# ePaperShoe.net
KiCad netlist of a schematic drawn in EAGLE
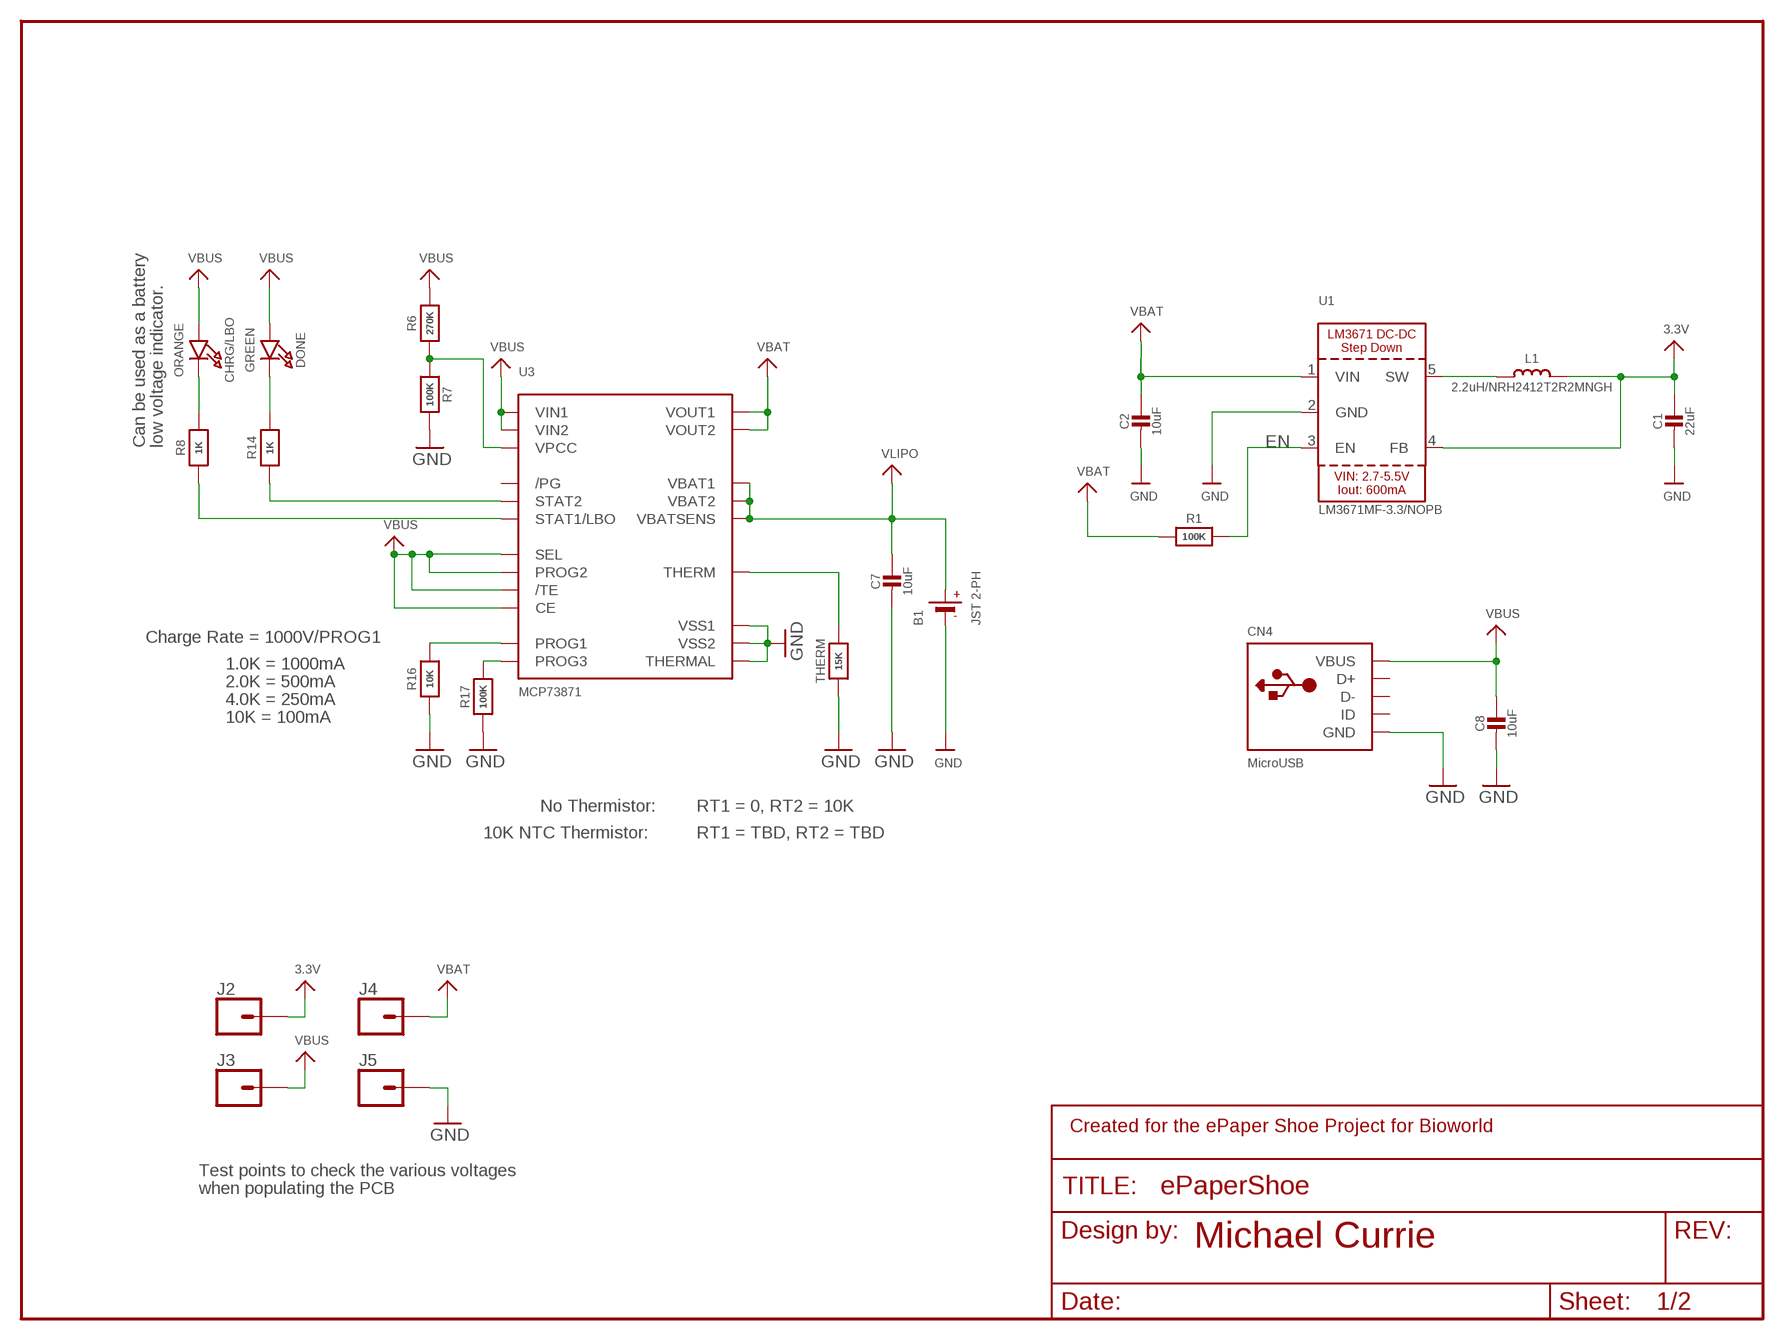
[diagram p0: schematic, sheet 1]
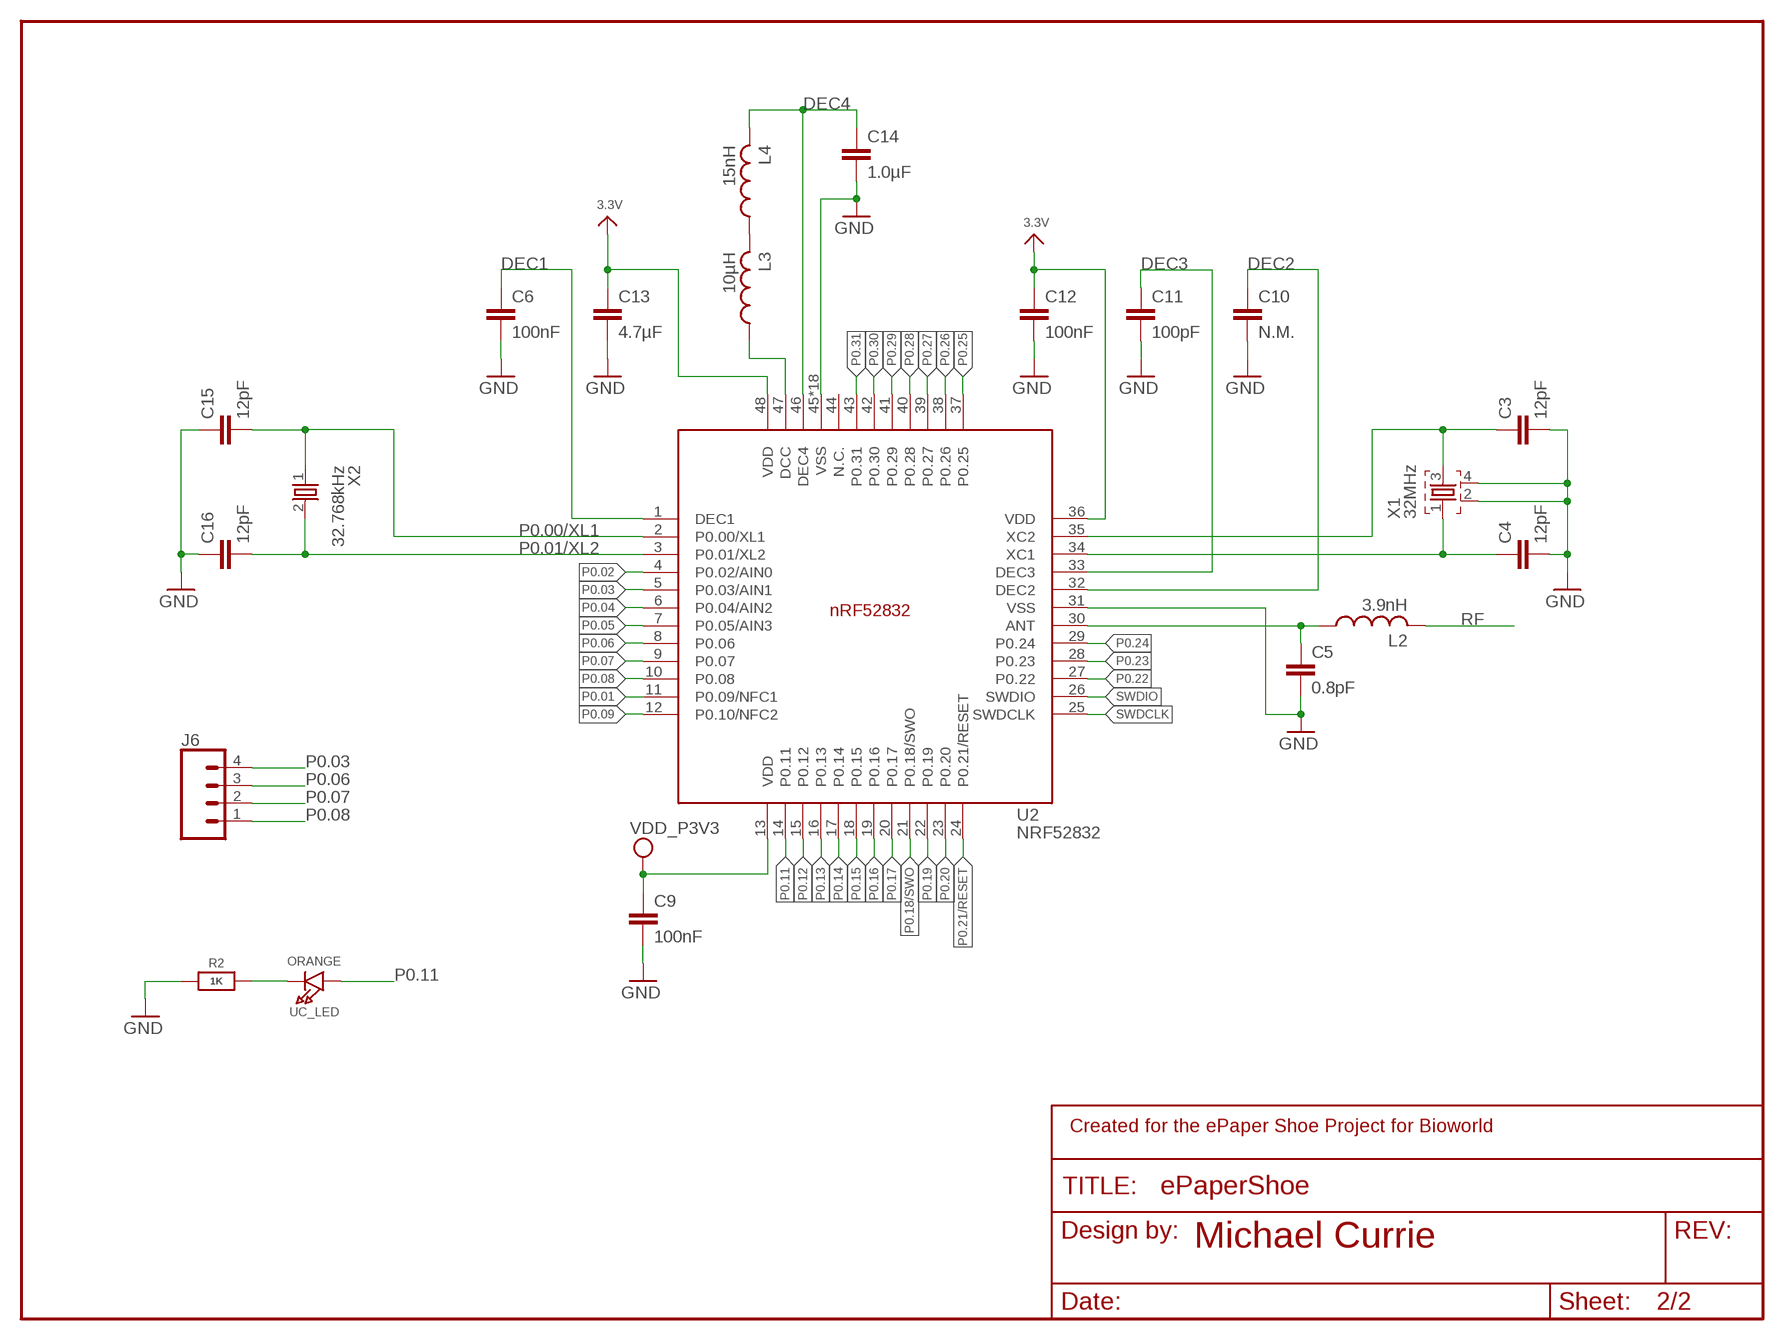
[diagram p1: schematic, sheet 2]

(export (version "E")
  (design (tool "Eeschema 10.0.6"))
  (components
    (comp (ref "B1")
      (value "JST 2-PH")
      (footprint "eagle-import:JSTPH2")
      (libsource (lib "eagle-import") (part "BATTERY"))
    )
    (comp (ref "C1")
      (value "22uF")
      (footprint "eagle-import:0805-NO")
      (libsource (lib "eagle-import") (part "CAP_CERAMIC0805-NOOUTLINE"))
    )
    (comp (ref "C2")
      (value "10uF")
      (footprint "eagle-import:0805-NO")
      (libsource (lib "eagle-import") (part "CAP_CERAMIC0805-NOOUTLINE"))
    )
    (comp (ref "C7")
      (value "10uF")
      (footprint "eagle-import:0805-NO")
      (libsource (lib "eagle-import") (part "CAP_CERAMIC0805-NOOUTLINE"))
    )
    (comp (ref "C8")
      (value "10uF")
      (footprint "eagle-import:0805-NO")
      (libsource (lib "eagle-import") (part "CAP_CERAMIC0805-NOOUTLINE"))
    )
    (comp (ref "CHRG/LBO")
      (value "ORANGE")
      (footprint "eagle-import:CHIPLED_0805_NOOUTLINE")
      (libsource (lib "eagle-import") (part "LED0805_NOOUTLINE"))
    )
    (comp (ref "CN4")
      (value "MicroUSB")
      (footprint "eagle-import:4UCONN_20329")
      (libsource (lib "eagle-import") (part "USBMICRO_20329"))
    )
    (comp (ref "DONE")
      (value "GREEN")
      (footprint "eagle-import:CHIPLED_0805_NOOUTLINE")
      (libsource (lib "eagle-import") (part "LED0805_NOOUTLINE"))
    )
    (comp (ref "FRAME1")
      (value "FRAME-LETTER-MICHAELNO_PACKAGE")
      (footprint "eagle-import:DUMMY")
      (fields (field (name "DESIGNER") "Nobody"))
      (libsource (lib "eagle-import") (part "FRAME-LETTER-MICHAELNO_PACKAGE"))
    )
    (comp (ref "J2")
      (value "CONN_01")
      (footprint "eagle-import:1X01")
      (libsource (lib "eagle-import") (part "CONN_01"))
    )
    (comp (ref "J3")
      (value "CONN_01")
      (footprint "eagle-import:1X01")
      (libsource (lib "eagle-import") (part "CONN_01"))
    )
    (comp (ref "J4")
      (value "CONN_01")
      (footprint "eagle-import:1X01")
      (libsource (lib "eagle-import") (part "CONN_01"))
    )
    (comp (ref "J5")
      (value "CONN_01")
      (footprint "eagle-import:1X01")
      (libsource (lib "eagle-import") (part "CONN_01"))
    )
    (comp (ref "L1")
      (value "2.2uH/NRH2412T2R2MNGH")
      (footprint "eagle-import:INDUCTOR_TAIYOYUDEN_NRH2412T")
      (libsource (lib "eagle-import") (part "INDUCTORNRH2412T"))
    )
    (comp (ref "R1")
      (value "100K")
      (footprint "eagle-import:0805-NO")
      (libsource (lib "eagle-import") (part "RESISTOR0805_NOOUTLINE"))
    )
    (comp (ref "R6")
      (value "270K")
      (footprint "eagle-import:0805-NO")
      (libsource (lib "eagle-import") (part "RESISTOR0805_NOOUTLINE"))
    )
    (comp (ref "R7")
      (value "100K")
      (footprint "eagle-import:0805-NO")
      (libsource (lib "eagle-import") (part "RESISTOR0805_NOOUTLINE"))
    )
    (comp (ref "R8")
      (value "1K")
      (footprint "eagle-import:0805-NO")
      (libsource (lib "eagle-import") (part "RESISTOR0805_NOOUTLINE"))
    )
    (comp (ref "R14")
      (value "1K")
      (footprint "eagle-import:0805-NO")
      (libsource (lib "eagle-import") (part "RESISTOR0805_NOOUTLINE"))
    )
    (comp (ref "R16")
      (value "10K")
      (footprint "eagle-import:0805-NO")
      (libsource (lib "eagle-import") (part "RESISTOR0805_NOOUTLINE"))
    )
    (comp (ref "R17")
      (value "100K")
      (footprint "eagle-import:0805-NO")
      (libsource (lib "eagle-import") (part "RESISTOR0805_NOOUTLINE"))
    )
    (comp (ref "THERM")
      (value "15K")
      (footprint "eagle-import:0805-NO")
      (libsource (lib "eagle-import") (part "RESISTOR0805_NOOUTLINE"))
    )
    (comp (ref "U1")
      (value "LM3671MF-3.3/NOPB")
      (footprint "eagle-import:SOT23-5")
      (libsource (lib "eagle-import") (part "VREG_LM3671"))
    )
    (comp (ref "U3")
      (value "MCP73871")
      (footprint "eagle-import:QFN20_4MM")
      (libsource (lib "eagle-import") (part "MCP73871"))
    )
    (comp (ref "C3")
      (value "12pF")
      (footprint "eagle-import:RESC0402_N")
      (libsource (lib "eagle-import") (part "CAPACITOR_0402_N"))
    )
    (comp (ref "C4")
      (value "12pF")
      (footprint "eagle-import:RESC0402_N")
      (libsource (lib "eagle-import") (part "CAPACITOR_0402_N"))
    )
    (comp (ref "C5")
      (value "0.8pF")
      (footprint "eagle-import:RESC0402_N")
      (libsource (lib "eagle-import") (part "CAPACITOR_0402_N"))
    )
    (comp (ref "C6")
      (value "100nF")
      (footprint "eagle-import:RESC0402_N")
      (libsource (lib "eagle-import") (part "CAPACITOR_0402_N"))
    )
    (comp (ref "C9")
      (value "100nF")
      (footprint "eagle-import:RESC0402_N")
      (libsource (lib "eagle-import") (part "CAPACITOR_0402_N"))
    )
    (comp (ref "C10")
      (value "N.M.")
      (footprint "eagle-import:RESC0402_N")
      (libsource (lib "eagle-import") (part "CAPACITOR_0402_N"))
    )
    (comp (ref "C11")
      (value "100pF")
      (footprint "eagle-import:RESC0402_N")
      (libsource (lib "eagle-import") (part "CAPACITOR_0402_N"))
    )
    (comp (ref "C12")
      (value "100nF")
      (footprint "eagle-import:RESC0402_N")
      (libsource (lib "eagle-import") (part "CAPACITOR_0402_N"))
    )
    (comp (ref "C13")
      (value "4.7µF")
      (footprint "eagle-import:RESC0603_N")
      (libsource (lib "eagle-import") (part "CAPACITOR_0603_N"))
    )
    (comp (ref "C14")
      (value "1.0µF")
      (footprint "eagle-import:RESC0603_N")
      (libsource (lib "eagle-import") (part "CAPACITOR_0603_N"))
    )
    (comp (ref "C15")
      (value "12pF")
      (footprint "eagle-import:RESC0402_N")
      (libsource (lib "eagle-import") (part "CAPACITOR_0402_N"))
    )
    (comp (ref "C16")
      (value "12pF")
      (footprint "eagle-import:RESC0402_N")
      (libsource (lib "eagle-import") (part "CAPACITOR_0402_N"))
    )
    (comp (ref "FRAME2")
      (value "FRAME-LETTER-MICHAELNO_PACKAGE")
      (footprint "eagle-import:DUMMY")
      (fields (field (name "DESIGNER") "Nobody"))
      (libsource (lib "eagle-import") (part "FRAME-LETTER-MICHAELNO_PACKAGE"))
    )
    (comp (ref "J6")
      (value "CONN_04")
      (footprint "eagle-import:1X04")
      (libsource (lib "eagle-import") (part "CONN_04"))
    )
    (comp (ref "L2")
      (value "3.9nH")
      (footprint "eagle-import:RESC0402_N")
      (libsource (lib "eagle-import") (part "INDUCTOR_0402_N"))
    )
    (comp (ref "L3")
      (value "10µH")
      (footprint "eagle-import:RESC0603_N")
      (libsource (lib "eagle-import") (part "INDUCTOR_0603_N"))
    )
    (comp (ref "L4")
      (value "15nH")
      (footprint "eagle-import:RESC0402_N")
      (libsource (lib "eagle-import") (part "INDUCTOR_0402_N"))
    )
    (comp (ref "R2")
      (value "1K")
      (footprint "eagle-import:0805-NO")
      (libsource (lib "eagle-import") (part "RESISTOR0805_NOOUTLINE"))
    )
    (comp (ref "U2")
      (value "NRF52832")
      (footprint "eagle-import:QFN40P600X600X90-48_N")
      (libsource (lib "eagle-import") (part "NRF52832"))
    )
    (comp (ref "UC_LED")
      (value "ORANGE")
      (footprint "eagle-import:CHIPLED_0805_NOOUTLINE")
      (libsource (lib "eagle-import") (part "LED0805_NOOUTLINE"))
    )
    (comp (ref "X1")
      (value "32MHz")
      (footprint "eagle-import:BT-XTAL_2016_N")
      (libsource (lib "eagle-import") (part "XTAL_32MHZ"))
    )
    (comp (ref "X2")
      (value "32.768kHz")
      (footprint "eagle-import:XTAL_3215_N")
      (libsource (lib "eagle-import") (part "XTAL_32KHZ"))
    )
  )
  (nets
    (net (code "1") (name "3.3V") (class "Default")
      (node (ref "C1") (pin "1") (pinfunction "1_1") (pintype "passive"))
      (node (ref "C12") (pin "1") (pinfunction "1_1") (pintype "passive"))
      (node (ref "C13") (pin "1") (pinfunction "1_1") (pintype "passive"))
      (node (ref "J2") (pin "1") (pinfunction "1_1") (pintype "passive"))
      (node (ref "L1") (pin "2") (pinfunction "2_2") (pintype "passive"))
      (node (ref "U1") (pin "4") (pinfunction "FB_4") (pintype "power_in"))
      (node (ref "U2") (pin "36") (pinfunction "VDD_36") (pintype "power_in"))
      (node (ref "U2") (pin "48") (pinfunction "VDD_48") (pintype "power_in"))
    )
    (net (code "2") (name "DEC1") (class "Default")
      (node (ref "C6") (pin "1") (pinfunction "1_1") (pintype "passive"))
      (node (ref "U2") (pin "1") (pinfunction "DEC1_1") (pintype "power_in"))
    )
    (net (code "3") (name "DEC2") (class "Default")
      (node (ref "C10") (pin "1") (pinfunction "1_1") (pintype "passive"))
      (node (ref "U2") (pin "32") (pinfunction "DEC2_32") (pintype "bidirectional"))
    )
    (net (code "4") (name "DEC3") (class "Default")
      (node (ref "C11") (pin "1") (pinfunction "1_1") (pintype "passive"))
      (node (ref "U2") (pin "33") (pinfunction "DEC3_33") (pintype "bidirectional"))
    )
    (net (code "5") (name "DEC4") (class "Default")
      (node (ref "C14") (pin "1") (pinfunction "1_1") (pintype "passive"))
      (node (ref "L4") (pin "2") (pinfunction "2_2") (pintype "passive"))
      (node (ref "U2") (pin "46") (pinfunction "DEC4_46") (pintype "power_in"))
    )
    (net (code "6") (name "EN") (class "Default")
      (node (ref "R1") (pin "2") (pinfunction "2_2") (pintype "passive"))
      (node (ref "U1") (pin "3") (pinfunction "EN_3") (pintype "input"))
    )
    (net (code "7") (name "GND") (class "Default")
      (node (ref "B1") (pin "1") (pinfunction "-_1") (pintype "passive"))
      (node (ref "C1") (pin "2") (pinfunction "2_2") (pintype "passive"))
      (node (ref "C10") (pin "2") (pinfunction "2_2") (pintype "passive"))
      (node (ref "C11") (pin "2") (pinfunction "2_2") (pintype "passive"))
      (node (ref "C12") (pin "2") (pinfunction "2_2") (pintype "passive"))
      (node (ref "C13") (pin "2") (pinfunction "2_2") (pintype "passive"))
      (node (ref "C14") (pin "2") (pinfunction "2_2") (pintype "passive"))
      (node (ref "C15") (pin "1") (pinfunction "1_1") (pintype "passive"))
      (node (ref "C16") (pin "1") (pinfunction "1_1") (pintype "passive"))
      (node (ref "C2") (pin "2") (pinfunction "2_2") (pintype "passive"))
      (node (ref "C3") (pin "2") (pinfunction "2_2") (pintype "passive"))
      (node (ref "C4") (pin "2") (pinfunction "2_2") (pintype "passive"))
      (node (ref "C5") (pin "2") (pinfunction "2_2") (pintype "passive"))
      (node (ref "C6") (pin "2") (pinfunction "2_2") (pintype "passive"))
      (node (ref "C7") (pin "2") (pinfunction "2_2") (pintype "passive"))
      (node (ref "C8") (pin "2") (pinfunction "2_2") (pintype "passive"))
      (node (ref "C9") (pin "2") (pinfunction "2_2") (pintype "passive"))
      (node (ref "CN4") (pin "BASE@1") (pinfunction "GND_BASE@1") (pintype "power_in"))
      (node (ref "CN4") (pin "BASE@2") (pinfunction "GND_BASE@2") (pintype "power_in"))
      (node (ref "CN4") (pin "GND") (pinfunction "GND_GND") (pintype "power_in"))
      (node (ref "CN4") (pin "SPRT@1") (pinfunction "GND_SPRT@1") (pintype "power_in"))
      (node (ref "CN4") (pin "SPRT@2") (pinfunction "GND_SPRT@2") (pintype "power_in"))
      (node (ref "CN4") (pin "SPRT@3") (pinfunction "GND_SPRT@3") (pintype "power_in"))
      (node (ref "CN4") (pin "SPRT@4") (pinfunction "GND_SPRT@4") (pintype "power_in"))
      (node (ref "J5") (pin "1") (pinfunction "1_1") (pintype "passive"))
      (node (ref "R16") (pin "1") (pinfunction "1_1") (pintype "passive"))
      (node (ref "R17") (pin "1") (pinfunction "1_1") (pintype "passive"))
      (node (ref "R2") (pin "1") (pinfunction "1_1") (pintype "passive"))
      (node (ref "R7") (pin "2") (pinfunction "2_2") (pintype "passive"))
      (node (ref "THERM") (pin "1") (pinfunction "1_1") (pintype "passive"))
      (node (ref "U1") (pin "2") (pinfunction "GND_2") (pintype "power_in"))
      (node (ref "U2") (pin "31") (pinfunction "VSS_31") (pintype "bidirectional"))
      (node (ref "U2") (pin "45") (pinfunction "VSS_45") (pintype "power_in"))
      (node (ref "U2") (pin "PAD") (pinfunction "VSS_PAD") (pintype "power_in"))
      (node (ref "U2") (pin "PAD@VIA01") (pinfunction "VSS_PAD@VIA01") (pintype "power_in"))
      (node (ref "U2") (pin "PAD@VIA02") (pinfunction "VSS_PAD@VIA02") (pintype "power_in"))
      (node (ref "U2") (pin "PAD@VIA03") (pinfunction "VSS_PAD@VIA03") (pintype "power_in"))
      (node (ref "U2") (pin "PAD@VIA04") (pinfunction "VSS_PAD@VIA04") (pintype "power_in"))
      (node (ref "U2") (pin "PAD@VIA05") (pinfunction "VSS_PAD@VIA05") (pintype "power_in"))
      (node (ref "U2") (pin "PAD@VIA06") (pinfunction "VSS_PAD@VIA06") (pintype "power_in"))
      (node (ref "U2") (pin "PAD@VIA07") (pinfunction "VSS_PAD@VIA07") (pintype "power_in"))
      (node (ref "U2") (pin "PAD@VIA08") (pinfunction "VSS_PAD@VIA08") (pintype "power_in"))
      (node (ref "U2") (pin "PAD@VIA09") (pinfunction "VSS_PAD@VIA09") (pintype "power_in"))
      (node (ref "U2") (pin "PAD@VIA10") (pinfunction "VSS_PAD@VIA10") (pintype "power_in"))
      (node (ref "U2") (pin "PAD@VIA11") (pinfunction "VSS_PAD@VIA11") (pintype "power_in"))
      (node (ref "U2") (pin "PAD@VIA12") (pinfunction "VSS_PAD@VIA12") (pintype "power_in"))
      (node (ref "U2") (pin "PAD@VIA13") (pinfunction "VSS_PAD@VIA13") (pintype "power_in"))
      (node (ref "U2") (pin "PAD@VIA14") (pinfunction "VSS_PAD@VIA14") (pintype "power_in"))
      (node (ref "U2") (pin "PAD@VIA15") (pinfunction "VSS_PAD@VIA15") (pintype "power_in"))
      (node (ref "U2") (pin "PAD@VIA16") (pinfunction "VSS_PAD@VIA16") (pintype "power_in"))
      (node (ref "U3") (pin "P$10") (pinfunction "VSS1_P$10") (pintype "bidirectional"))
      (node (ref "U3") (pin "P$11") (pinfunction "VSS2_P$11") (pintype "bidirectional"))
      (node (ref "U3") (pin "P$21") (pinfunction "THERMAL_P$21") (pintype "bidirectional"))
      (node (ref "X1") (pin "2") (pinfunction "2_2") (pintype "passive"))
      (node (ref "X1") (pin "4") (pinfunction "4_4") (pintype "passive"))
    )
    (net (code "8") (name "Net-(CHRG/LBO-PadC)") (class "Default")
      (node (ref "CHRG/LBO") (pin "C") (pinfunction "C_C") (pintype "passive"))
      (node (ref "R8") (pin "2") (pinfunction "2_2") (pintype "passive"))
    )
    (net (code "9") (name "Net-(DONE-PadC)") (class "Default")
      (node (ref "DONE") (pin "C") (pinfunction "C_C") (pintype "passive"))
      (node (ref "R14") (pin "2") (pinfunction "2_2") (pintype "passive"))
    )
    (net (code "10") (name "Net-(L3-Pad2)") (class "Default")
      (node (ref "L3") (pin "2") (pinfunction "2_2") (pintype "passive"))
      (node (ref "L4") (pin "1") (pinfunction "1_1") (pintype "passive"))
    )
    (net (code "11") (name "Net-(R2-Pad2)") (class "Default")
      (node (ref "R2") (pin "2") (pinfunction "2_2") (pintype "passive"))
      (node (ref "UC_LED") (pin "C") (pinfunction "C_C") (pintype "passive"))
    )
    (net (code "12") (name "Net-(U1-SW)") (class "Default")
      (node (ref "L1") (pin "1") (pinfunction "1_1") (pintype "passive"))
      (node (ref "U1") (pin "5") (pinfunction "SW_5") (pintype "output"))
    )
    (net (code "13") (name "Net-(U2-ANT)") (class "Default")
      (node (ref "C5") (pin "1") (pinfunction "1_1") (pintype "passive"))
      (node (ref "L2") (pin "1") (pinfunction "1_1") (pintype "passive"))
      (node (ref "U2") (pin "30") (pinfunction "ANT_30") (pintype "bidirectional"))
    )
    (net (code "14") (name "Net-(U2-DCC)") (class "Default")
      (node (ref "L3") (pin "1") (pinfunction "1_1") (pintype "passive"))
      (node (ref "U2") (pin "47") (pinfunction "DCC_47") (pintype "output"))
    )
    (net (code "15") (name "Net-(U2-XC1)") (class "Default")
      (node (ref "C4") (pin "1") (pinfunction "1_1") (pintype "passive"))
      (node (ref "U2") (pin "34") (pinfunction "XC1_34") (pintype "input"))
      (node (ref "X1") (pin "1") (pinfunction "1_1") (pintype "passive"))
    )
    (net (code "16") (name "Net-(U2-XC2)") (class "Default")
      (node (ref "C3") (pin "1") (pinfunction "1_1") (pintype "passive"))
      (node (ref "U2") (pin "35") (pinfunction "XC2_35") (pintype "output"))
      (node (ref "X1") (pin "3") (pinfunction "3_3") (pintype "passive"))
    )
    (net (code "17") (name "Net-(U3-PROG1)") (class "Default")
      (node (ref "R16") (pin "2") (pinfunction "2_2") (pintype "passive"))
      (node (ref "U3") (pin "P$13") (pinfunction "PROG1_P$13") (pintype "bidirectional"))
    )
    (net (code "18") (name "Net-(U3-PROG3)") (class "Default")
      (node (ref "R17") (pin "2") (pinfunction "2_2") (pintype "passive"))
      (node (ref "U3") (pin "P$12") (pinfunction "PROG3_P$12") (pintype "bidirectional"))
    )
    (net (code "19") (name "Net-(U3-STAT1{slash}LBO)") (class "Default")
      (node (ref "R8") (pin "1") (pinfunction "1_1") (pintype "passive"))
      (node (ref "U3") (pin "P$8") (pinfunction "STAT1/LBO_P$8") (pintype "bidirectional"))
    )
    (net (code "20") (name "Net-(U3-STAT2)") (class "Default")
      (node (ref "R14") (pin "1") (pinfunction "1_1") (pintype "passive"))
      (node (ref "U3") (pin "P$7") (pinfunction "STAT2_P$7") (pintype "bidirectional"))
    )
    (net (code "21") (name "Net-(U3-THERM)") (class "Default")
      (node (ref "THERM") (pin "2") (pinfunction "2_2") (pintype "passive"))
      (node (ref "U3") (pin "P$5") (pinfunction "THERM_P$5") (pintype "bidirectional"))
    )
    (net (code "22") (name "Net-(U3-VPCC)") (class "Default")
      (node (ref "R6") (pin "1") (pinfunction "1_1") (pintype "passive"))
      (node (ref "R7") (pin "1") (pinfunction "1_1") (pintype "passive"))
      (node (ref "U3") (pin "P$2") (pinfunction "VPCC_P$2") (pintype "bidirectional"))
    )
    (net (code "23") (name "P0.00{slash}XL1") (class "Default")
      (node (ref "C15") (pin "2") (pinfunction "2_2") (pintype "passive"))
      (node (ref "U2") (pin "2") (pinfunction "P0.00/XL1_2") (pintype "bidirectional"))
      (node (ref "X2") (pin "1") (pinfunction "1_1") (pintype "passive"))
    )
    (net (code "24") (name "P0.01") (class "Default")
      (node (ref "U2") (pin "11") (pinfunction "P0.09/NFC1_11") (pintype "bidirectional"))
    )
    (net (code "25") (name "P0.01{slash}XL2") (class "Default")
      (node (ref "C16") (pin "2") (pinfunction "2_2") (pintype "passive"))
      (node (ref "U2") (pin "3") (pinfunction "P0.01/XL2_3") (pintype "bidirectional"))
      (node (ref "X2") (pin "2") (pinfunction "2_2") (pintype "passive"))
    )
    (net (code "26") (name "P0.02") (class "Default")
      (node (ref "U2") (pin "4") (pinfunction "P0.02/AIN0_4") (pintype "bidirectional"))
    )
    (net (code "27") (name "P0.03") (class "Default")
      (node (ref "J6") (pin "4") (pinfunction "4_4") (pintype "passive"))
      (node (ref "U2") (pin "5") (pinfunction "P0.03/AIN1_5") (pintype "bidirectional"))
    )
    (net (code "28") (name "P0.04") (class "Default")
      (node (ref "U2") (pin "6") (pinfunction "P0.04/AIN2_6") (pintype "bidirectional"))
    )
    (net (code "29") (name "P0.05") (class "Default")
      (node (ref "U2") (pin "7") (pinfunction "P0.05/AIN3_7") (pintype "bidirectional"))
    )
    (net (code "30") (name "P0.06") (class "Default")
      (node (ref "J6") (pin "3") (pinfunction "3_3") (pintype "passive"))
      (node (ref "U2") (pin "8") (pinfunction "P0.06_8") (pintype "bidirectional"))
    )
    (net (code "31") (name "P0.07") (class "Default")
      (node (ref "J6") (pin "2") (pinfunction "2_2") (pintype "passive"))
      (node (ref "U2") (pin "9") (pinfunction "P0.07_9") (pintype "bidirectional"))
    )
    (net (code "32") (name "P0.08") (class "Default")
      (node (ref "J6") (pin "1") (pinfunction "1_1") (pintype "passive"))
      (node (ref "U2") (pin "10") (pinfunction "P0.08_10") (pintype "bidirectional"))
    )
    (net (code "33") (name "P0.09") (class "Default")
      (node (ref "U2") (pin "12") (pinfunction "P0.10/NFC2_12") (pintype "bidirectional"))
    )
    (net (code "34") (name "P0.11") (class "Default")
      (node (ref "U2") (pin "14") (pinfunction "P0.11_14") (pintype "bidirectional"))
      (node (ref "UC_LED") (pin "A") (pinfunction "A_A") (pintype "passive"))
    )
    (net (code "35") (name "P0.12") (class "Default")
      (node (ref "U2") (pin "15") (pinfunction "P0.12_15") (pintype "bidirectional"))
    )
    (net (code "36") (name "P0.13") (class "Default")
      (node (ref "U2") (pin "16") (pinfunction "P0.13_16") (pintype "bidirectional"))
    )
    (net (code "37") (name "P0.14") (class "Default")
      (node (ref "U2") (pin "17") (pinfunction "P0.14_17") (pintype "bidirectional"))
    )
    (net (code "38") (name "P0.15") (class "Default")
      (node (ref "U2") (pin "18") (pinfunction "P0.15_18") (pintype "bidirectional"))
    )
    (net (code "39") (name "P0.16") (class "Default")
      (node (ref "U2") (pin "19") (pinfunction "P0.16_19") (pintype "bidirectional"))
    )
    (net (code "40") (name "P0.17") (class "Default")
      (node (ref "U2") (pin "20") (pinfunction "P0.17_20") (pintype "bidirectional"))
    )
    (net (code "41") (name "P0.18{slash}SWO") (class "Default")
      (node (ref "U2") (pin "21") (pinfunction "P0.18/SWO_21") (pintype "bidirectional"))
    )
    (net (code "42") (name "P0.19") (class "Default")
      (node (ref "U2") (pin "22") (pinfunction "P0.19_22") (pintype "bidirectional"))
    )
    (net (code "43") (name "P0.20") (class "Default")
      (node (ref "U2") (pin "23") (pinfunction "P0.20_23") (pintype "bidirectional"))
    )
    (net (code "44") (name "P0.21{slash}RESET") (class "Default")
      (node (ref "U2") (pin "24") (pinfunction "P0.21/RESET_24") (pintype "bidirectional"))
    )
    (net (code "45") (name "P0.22") (class "Default")
      (node (ref "U2") (pin "27") (pinfunction "P0.22_27") (pintype "bidirectional"))
    )
    (net (code "46") (name "P0.23") (class "Default")
      (node (ref "U2") (pin "28") (pinfunction "P0.23_28") (pintype "bidirectional"))
    )
    (net (code "47") (name "P0.24") (class "Default")
      (node (ref "U2") (pin "29") (pinfunction "P0.24_29") (pintype "bidirectional"))
    )
    (net (code "48") (name "P0.25") (class "Default")
      (node (ref "U2") (pin "37") (pinfunction "P0.25_37") (pintype "bidirectional"))
    )
    (net (code "49") (name "P0.26") (class "Default")
      (node (ref "U2") (pin "38") (pinfunction "P0.26_38") (pintype "bidirectional"))
    )
    (net (code "50") (name "P0.27") (class "Default")
      (node (ref "U2") (pin "39") (pinfunction "P0.27_39") (pintype "bidirectional"))
    )
    (net (code "51") (name "P0.28") (class "Default")
      (node (ref "U2") (pin "40") (pinfunction "P0.28_40") (pintype "bidirectional"))
    )
    (net (code "52") (name "P0.29") (class "Default")
      (node (ref "U2") (pin "41") (pinfunction "P0.29_41") (pintype "bidirectional"))
    )
    (net (code "53") (name "P0.30") (class "Default")
      (node (ref "U2") (pin "42") (pinfunction "P0.30_42") (pintype "bidirectional"))
    )
    (net (code "54") (name "P0.31") (class "Default")
      (node (ref "U2") (pin "43") (pinfunction "P0.31_43") (pintype "bidirectional"))
    )
    (net (code "55") (name "RF") (class "Default")
      (node (ref "L2") (pin "2") (pinfunction "2_2") (pintype "passive"))
    )
    (net (code "56") (name "SWDCLK") (class "Default")
      (node (ref "U2") (pin "25") (pinfunction "SWDCLK_25") (pintype "input"))
    )
    (net (code "57") (name "SWDIO") (class "Default")
      (node (ref "U2") (pin "26") (pinfunction "SWDIO_26") (pintype "bidirectional"))
    )
    (net (code "58") (name "VBAT") (class "Default")
      (node (ref "C2") (pin "1") (pinfunction "1_1") (pintype "passive"))
      (node (ref "J4") (pin "1") (pinfunction "1_1") (pintype "passive"))
      (node (ref "R1") (pin "1") (pinfunction "1_1") (pintype "passive"))
      (node (ref "U1") (pin "1") (pinfunction "VIN_1") (pintype "power_in"))
      (node (ref "U3") (pin "P$1") (pinfunction "VOUT1_P$1") (pintype "bidirectional"))
      (node (ref "U3") (pin "P$20") (pinfunction "VOUT2_P$20") (pintype "bidirectional"))
    )
    (net (code "59") (name "VBUS") (class "Default")
      (node (ref "C8") (pin "1") (pinfunction "1_1") (pintype "passive"))
      (node (ref "CHRG/LBO") (pin "A") (pinfunction "A_A") (pintype "passive"))
      (node (ref "CN4") (pin "VBUS") (pinfunction "VBUS_VBUS") (pintype "power_in"))
      (node (ref "DONE") (pin "A") (pinfunction "A_A") (pintype "passive"))
      (node (ref "J3") (pin "1") (pinfunction "1_1") (pintype "passive"))
      (node (ref "R6") (pin "2") (pinfunction "2_2") (pintype "passive"))
      (node (ref "U3") (pin "P$17") (pinfunction "CE_P$17") (pintype "bidirectional"))
      (node (ref "U3") (pin "P$18") (pinfunction "VIN1_P$18") (pintype "bidirectional"))
      (node (ref "U3") (pin "P$19") (pinfunction "VIN2_P$19") (pintype "bidirectional"))
      (node (ref "U3") (pin "P$3") (pinfunction "SEL_P$3") (pintype "bidirectional"))
      (node (ref "U3") (pin "P$4") (pinfunction "PROG2_P$4") (pintype "bidirectional"))
      (node (ref "U3") (pin "P$9") (pinfunction "/TE_P$9") (pintype "bidirectional"))
    )
    (net (code "60") (name "VDD_P3V3") (class "Default")
      (node (ref "C9") (pin "1") (pinfunction "1_1") (pintype "passive"))
      (node (ref "U2") (pin "13") (pinfunction "VDD_13") (pintype "power_in"))
    )
    (net (code "61") (name "VLIPO") (class "Default")
      (node (ref "B1") (pin "2") (pinfunction "+_2") (pintype "passive"))
      (node (ref "C7") (pin "1") (pinfunction "1_1") (pintype "passive"))
      (node (ref "U3") (pin "P$14") (pinfunction "VBAT1_P$14") (pintype "bidirectional"))
      (node (ref "U3") (pin "P$15") (pinfunction "VBAT2_P$15") (pintype "bidirectional"))
      (node (ref "U3") (pin "P$16") (pinfunction "VBATSENS_P$16") (pintype "bidirectional"))
    )
    (net (code "62") (name "unconnected-(CN4-PadD+)") (class "Default")
      (node (ref "CN4") (pin "D+") (pinfunction "D+_D+") (pintype "bidirectional"))
    )
    (net (code "63") (name "unconnected-(CN4-PadD-)") (class "Default")
      (node (ref "CN4") (pin "D-") (pinfunction "D-_D-") (pintype "bidirectional"))
    )
    (net (code "64") (name "unconnected-(CN4-PadID)") (class "Default")
      (node (ref "CN4") (pin "ID") (pinfunction "ID_ID") (pintype "bidirectional"))
    )
    (net (code "65") (name "unconnected-(U2-N.C.-Pad44)") (class "Default")
      (node (ref "U2") (pin "44") (pinfunction "N.C._44") (pintype "no_connect"))
    )
    (net (code "66") (name "unconnected-(U3-{slash}PG-PadP$6)") (class "Default")
      (node (ref "U3") (pin "P$6") (pinfunction "/PG_P$6") (pintype "bidirectional"))
    )
  )
)
